# audioAmp.net
KiCad netlist of a schematic drawn in EAGLE
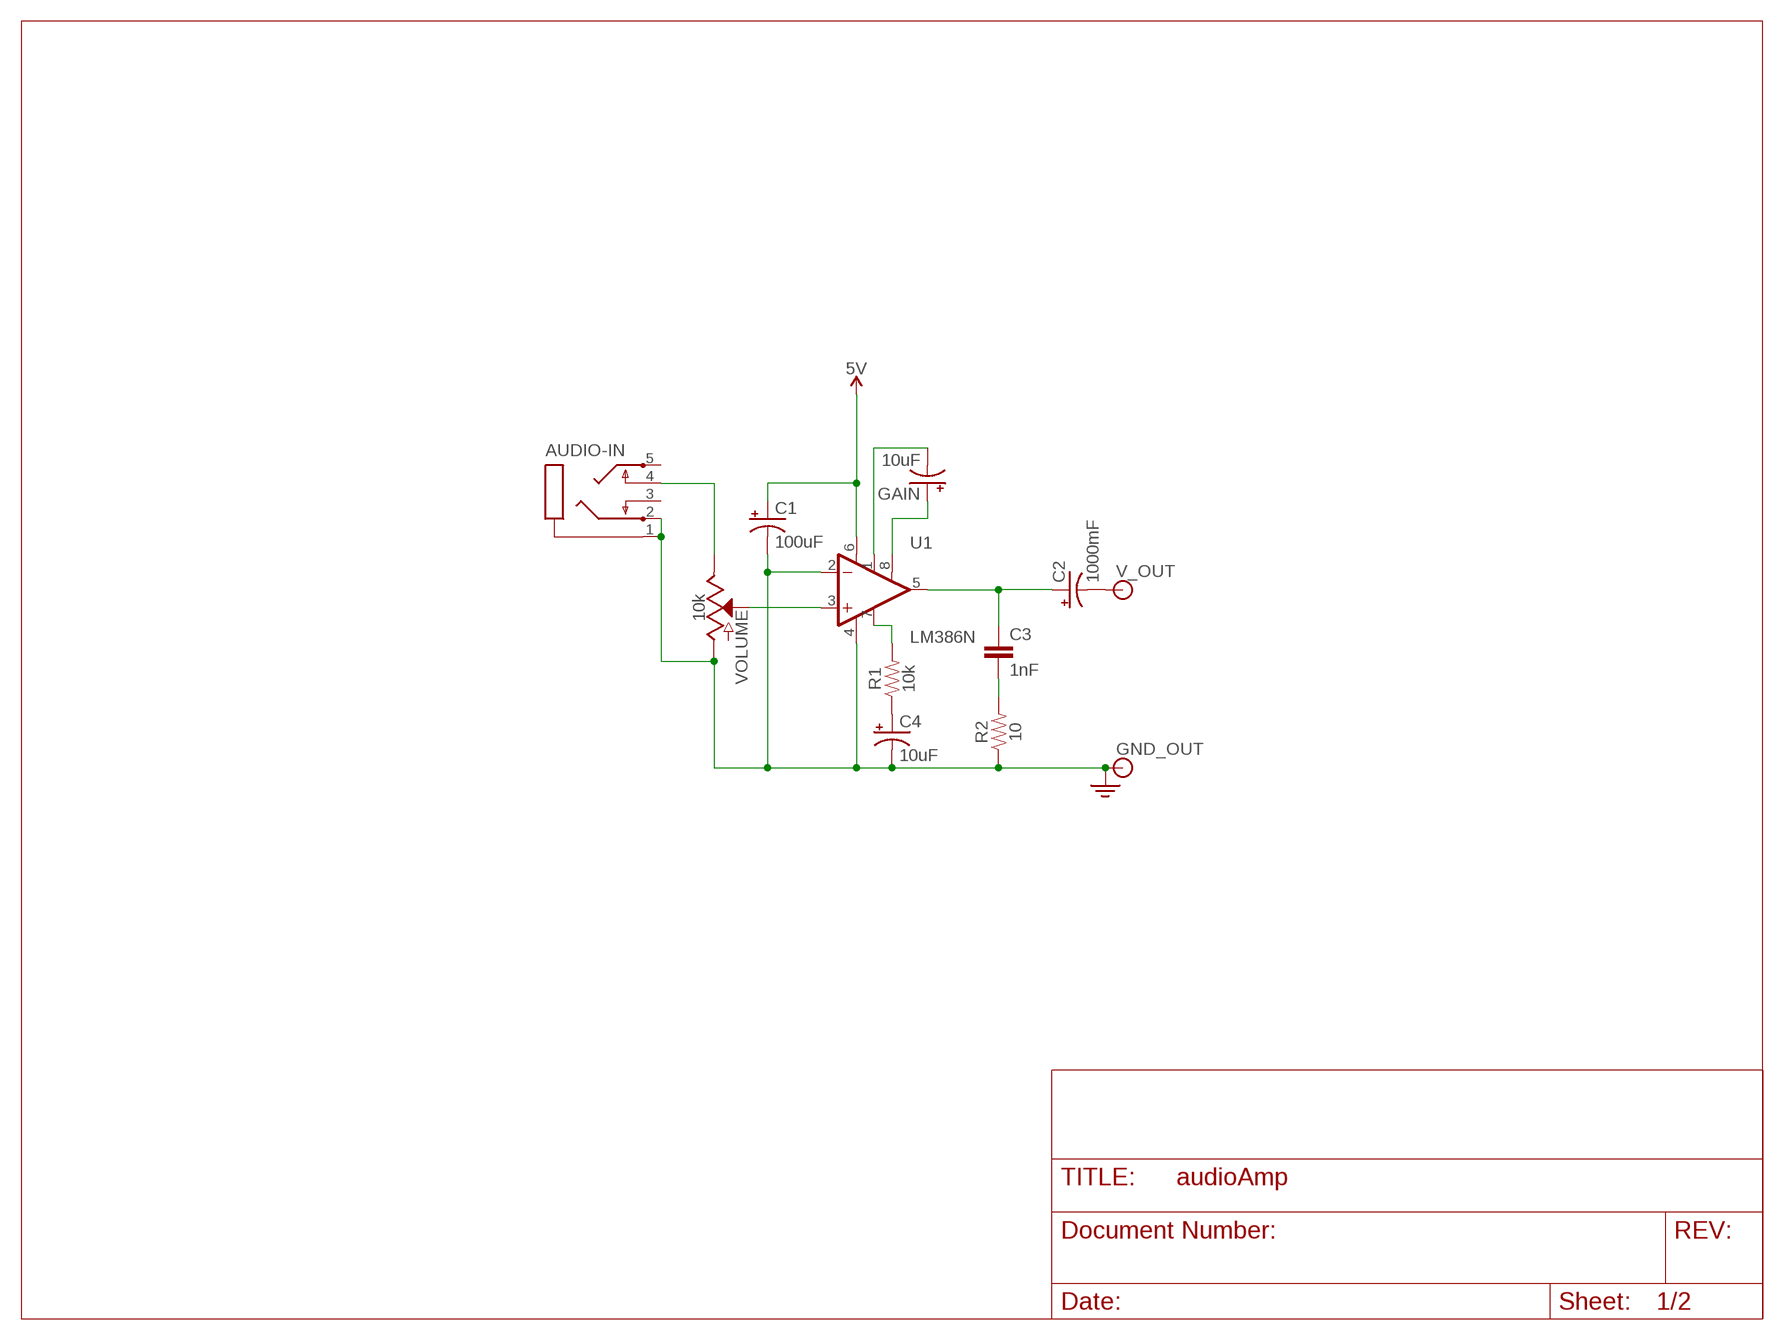
[diagram p0: schematic, sheet 1]
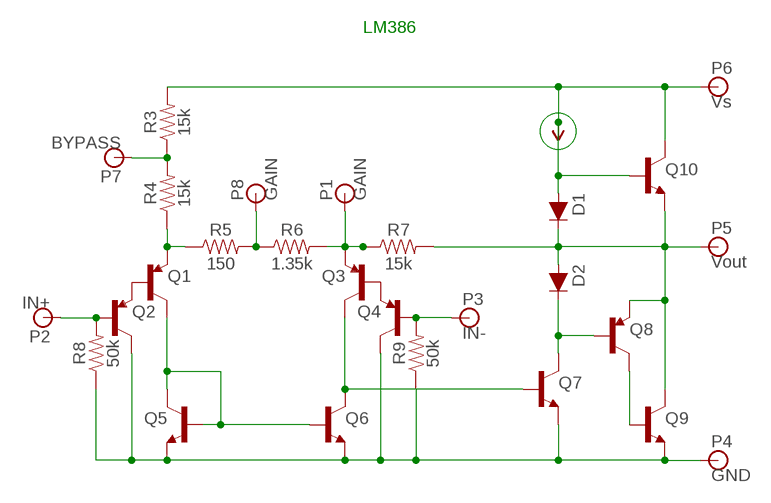
[diagram p1: schematic, sheet 2]

(export (version "E")
  (design (tool "Eeschema 10.0.6"))
  (components
    (comp (ref "D1")
      (value "DIODE-1N4148")
      (footprint "eagle-import:DIODE-1N4148")
      (libsource (lib "eagle-import") (part "DIODE-1N4148"))
    )
    (comp (ref "D2")
      (value "DIODE-1N4148")
      (footprint "eagle-import:DIODE-1N4148")
      (libsource (lib "eagle-import") (part "DIODE-1N4148"))
    )
    (comp (ref "P1")
      (value "GAIN")
      (footprint "eagle-import:BANANA_CONN")
      (libsource (lib "eagle-import") (part "BANANA_CONN"))
    )
    (comp (ref "P2")
      (value "IN+")
      (footprint "eagle-import:BANANA_CONN")
      (libsource (lib "eagle-import") (part "BANANA_CONN"))
    )
    (comp (ref "P3")
      (value "IN-")
      (footprint "eagle-import:BANANA_CONN")
      (libsource (lib "eagle-import") (part "BANANA_CONN"))
    )
    (comp (ref "P4")
      (value "GND")
      (footprint "eagle-import:BANANA_CONN")
      (libsource (lib "eagle-import") (part "BANANA_CONN"))
    )
    (comp (ref "P5")
      (value "Vout")
      (footprint "eagle-import:BANANA_CONN")
      (libsource (lib "eagle-import") (part "BANANA_CONN"))
    )
    (comp (ref "P6")
      (value "Vs")
      (footprint "eagle-import:BANANA_CONN")
      (libsource (lib "eagle-import") (part "BANANA_CONN"))
    )
    (comp (ref "P7")
      (value "BYPASS")
      (footprint "eagle-import:BANANA_CONN")
      (libsource (lib "eagle-import") (part "BANANA_CONN"))
    )
    (comp (ref "P8")
      (value "GAIN")
      (footprint "eagle-import:BANANA_CONN")
      (libsource (lib "eagle-import") (part "BANANA_CONN"))
    )
    (comp (ref "Q1")
      (value "TRANS_PNP-MMBT4403")
      (footprint "eagle-import:SOT23-3")
      (libsource (lib "eagle-import") (part "TRANS_PNP-MMBT4403"))
    )
    (comp (ref "Q2")
      (value "TRANS_PNP-MMBT4403")
      (footprint "eagle-import:SOT23-3")
      (libsource (lib "eagle-import") (part "TRANS_PNP-MMBT4403"))
    )
    (comp (ref "Q3")
      (value "TRANS_PNP-MMBT4403")
      (footprint "eagle-import:SOT23-3")
      (libsource (lib "eagle-import") (part "TRANS_PNP-MMBT4403"))
    )
    (comp (ref "Q4")
      (value "TRANS_PNP-MMBT4403")
      (footprint "eagle-import:SOT23-3")
      (libsource (lib "eagle-import") (part "TRANS_PNP-MMBT4403"))
    )
    (comp (ref "Q5")
      (value "TRANS_NPN-MMBT2222AL")
      (footprint "eagle-import:SOT23-3")
      (libsource (lib "eagle-import") (part "TRANS_NPN-MMBT2222AL"))
    )
    (comp (ref "Q6")
      (value "TRANS_NPN-MMBT2222AL")
      (footprint "eagle-import:SOT23-3")
      (libsource (lib "eagle-import") (part "TRANS_NPN-MMBT2222AL"))
    )
    (comp (ref "Q7")
      (value "TRANS_NPN-MMBT2222AL")
      (footprint "eagle-import:SOT23-3")
      (libsource (lib "eagle-import") (part "TRANS_NPN-MMBT2222AL"))
    )
    (comp (ref "Q8")
      (value "TRANS_PNP-MMBT4403")
      (footprint "eagle-import:SOT23-3")
      (libsource (lib "eagle-import") (part "TRANS_PNP-MMBT4403"))
    )
    (comp (ref "Q9")
      (value "TRANS_NPN-MMBT2222AL")
      (footprint "eagle-import:SOT23-3")
      (libsource (lib "eagle-import") (part "TRANS_NPN-MMBT2222AL"))
    )
    (comp (ref "Q10")
      (value "TRANS_NPN-MMBT2222AL")
      (footprint "eagle-import:SOT23-3")
      (libsource (lib "eagle-import") (part "TRANS_NPN-MMBT2222AL"))
    )
    (comp (ref "R3")
      (value "15k")
      (footprint "eagle-import:AXIAL-0.3")
      (libsource (lib "eagle-import") (part "15KOHM-HORIZ-1/4W-5%"))
    )
    (comp (ref "R4")
      (value "15k")
      (footprint "eagle-import:AXIAL-0.3")
      (libsource (lib "eagle-import") (part "15KOHM-HORIZ-1/4W-5%"))
    )
    (comp (ref "R5")
      (value "150")
      (footprint "eagle-import:AXIAL-0.3")
      (libsource (lib "eagle-import") (part "RESISTORAXIAL-0.3"))
    )
    (comp (ref "R6")
      (value "1.35k")
      (footprint "eagle-import:AXIAL-0.3")
      (libsource (lib "eagle-import") (part "RESISTORAXIAL-0.3"))
    )
    (comp (ref "R7")
      (value "15k")
      (footprint "eagle-import:AXIAL-0.3")
      (libsource (lib "eagle-import") (part "RESISTORAXIAL-0.3"))
    )
    (comp (ref "R8")
      (value "50k")
      (footprint "eagle-import:AXIAL-0.3")
      (libsource (lib "eagle-import") (part "RESISTORAXIAL-0.3"))
    )
    (comp (ref "R9")
      (value "50k")
      (footprint "eagle-import:AXIAL-0.3")
      (libsource (lib "eagle-import") (part "RESISTORAXIAL-0.3"))
    )
    (comp (ref "AUDIO-IN")
      (value "STEREOJACK")
      (footprint "eagle-import:STX3100")
      (libsource (lib "eagle-import") (part "STEREOJACK"))
    )
    (comp (ref "C1")
      (value "100uF")
      (footprint "eagle-import:CPOL-RADIAL-2.5MM-6.5MM")
      (libsource (lib "eagle-import") (part "100UF-POLAR-RADIAL-2.5MM-25V-20%"))
    )
    (comp (ref "C2")
      (value "1000mF")
      (footprint "eagle-import:CPOL-RADIAL-5MM-10MM")
      (libsource (lib "eagle-import") (part "1000UF-RADIAL-5MM-25V-20%"))
    )
    (comp (ref "C3")
      (value "1nF")
      (footprint "eagle-import:0603")
      (libsource (lib "eagle-import") (part "1.0NF/1000PF-0603-50V-10%"))
    )
    (comp (ref "C4")
      (value "10uF")
      (footprint "eagle-import:CPOL-RADIAL-2.5MM-5MM")
      (libsource (lib "eagle-import") (part "10UF-POLAR-RADIAL-2.5MM-25V-20%"))
    )
    (comp (ref "GAIN")
      (value "10uF")
      (footprint "eagle-import:CPOL-RADIAL-2.5MM-5MM")
      (libsource (lib "eagle-import") (part "10UF-POLAR-RADIAL-2.5MM-25V-20%"))
    )
    (comp (ref "GND_OUT")
      (value "BANANA_CONN")
      (footprint "eagle-import:BANANA_CONN")
      (libsource (lib "eagle-import") (part "BANANA_CONN"))
    )
    (comp (ref "R1")
      (value "10k")
      (footprint "eagle-import:AXIAL-0.3")
      (libsource (lib "eagle-import") (part "10KOHM-HORIZ-1/4W-1%"))
    )
    (comp (ref "R2")
      (value "10")
      (footprint "eagle-import:AXIAL-0.3")
      (libsource (lib "eagle-import") (part "10OHM-HORIZ-1/4W-1%"))
    )
    (comp (ref "U1")
      (value "LM386N")
      (footprint "eagle-import:DIP08")
      (libsource (lib "eagle-import") (part "LM386"))
    )
    (comp (ref "VOLUME")
      (value "10k")
      (footprint "eagle-import:POT-PTH-ALPS")
      (libsource (lib "eagle-import") (part "POTENTIOMETER-PTH-9MM-1/20W-20%"))
    )
    (comp (ref "V_OUT")
      (value "BANANA_CONN")
      (footprint "eagle-import:BANANA_CONN")
      (libsource (lib "eagle-import") (part "BANANA_CONN"))
    )
  )
  (nets
    (net (code "1") (name "5V") (class "Default")
      (node (ref "C1") (pin "1") (pinfunction "+_1") (pintype "passive"))
      (node (ref "U1") (pin "6") (pinfunction "V+_6") (pintype "power_in"))
    )
    (net (code "2") (name "GND2") (class "Default")
      (node (ref "AUDIO-IN") (pin "1") (pinfunction "1_1") (pintype "passive"))
      (node (ref "AUDIO-IN") (pin "2") (pinfunction "2_2") (pintype "passive"))
      (node (ref "C1") (pin "2") (pinfunction "-_2") (pintype "passive"))
      (node (ref "C4") (pin "2") (pinfunction "-_2") (pintype "passive"))
      (node (ref "GND_OUT") (pin "P$1") (pinfunction "1_P$1") (pintype "passive"))
      (node (ref "R2") (pin "P$1") (pinfunction "1_P$1") (pintype "passive"))
      (node (ref "U1") (pin "2") (pinfunction "-IN_2") (pintype "input"))
      (node (ref "U1") (pin "4") (pinfunction "V-_4") (pintype "power_in"))
      (node (ref "VOLUME") (pin "P$3") (pinfunction "A_P$3") (pintype "passive"))
    )
    (net (code "3") (name "Net-(C4-+)") (class "Default")
      (node (ref "C4") (pin "1") (pinfunction "+_1") (pintype "passive"))
      (node (ref "R1") (pin "P$1") (pinfunction "1_P$1") (pintype "passive"))
    )
    (net (code "4") (name "Net-(GAIN-+)") (class "Default")
      (node (ref "GAIN") (pin "1") (pinfunction "+_1") (pintype "passive"))
      (node (ref "U1") (pin "8") (pinfunction "GAIN_8") (pintype "bidirectional"))
    )
    (net (code "5") (name "Net-(GAIN--)") (class "Default")
      (node (ref "GAIN") (pin "2") (pinfunction "-_2") (pintype "passive"))
      (node (ref "U1") (pin "1") (pinfunction "GAIN_1") (pintype "bidirectional"))
    )
    (net (code "6") (name "Net-(P1-1)") (class "Default")
      (node (ref "P1") (pin "P$1") (pinfunction "1_P$1") (pintype "passive"))
      (node (ref "Q3") (pin "2") (pinfunction "E_2") (pintype "passive"))
      (node (ref "R6") (pin "P$2") (pinfunction "2_P$2") (pintype "passive"))
      (node (ref "R7") (pin "P$1") (pinfunction "1_P$1") (pintype "passive"))
    )
    (net (code "7") (name "Net-(P2-1)") (class "Default")
      (node (ref "P2") (pin "P$1") (pinfunction "1_P$1") (pintype "passive"))
      (node (ref "Q2") (pin "1") (pinfunction "B_1") (pintype "passive"))
      (node (ref "R8") (pin "P$2") (pinfunction "2_P$2") (pintype "passive"))
    )
    (net (code "8") (name "Net-(P3-1)") (class "Default")
      (node (ref "P3") (pin "P$1") (pinfunction "1_P$1") (pintype "passive"))
      (node (ref "Q4") (pin "1") (pinfunction "B_1") (pintype "passive"))
      (node (ref "R9") (pin "P$2") (pinfunction "2_P$2") (pintype "passive"))
    )
    (net (code "9") (name "Net-(P4-1)") (class "Default")
      (node (ref "P4") (pin "P$1") (pinfunction "1_P$1") (pintype "passive"))
      (node (ref "Q2") (pin "3") (pinfunction "C_3") (pintype "passive"))
      (node (ref "Q4") (pin "3") (pinfunction "C_3") (pintype "passive"))
      (node (ref "Q5") (pin "2") (pinfunction "E_2") (pintype "passive"))
      (node (ref "Q6") (pin "2") (pinfunction "E_2") (pintype "passive"))
      (node (ref "Q7") (pin "2") (pinfunction "E_2") (pintype "passive"))
      (node (ref "Q9") (pin "2") (pinfunction "E_2") (pintype "passive"))
      (node (ref "R8") (pin "P$1") (pinfunction "1_P$1") (pintype "passive"))
      (node (ref "R9") (pin "P$1") (pinfunction "1_P$1") (pintype "passive"))
    )
    (net (code "10") (name "Net-(P5-1)") (class "Default")
      (node (ref "D1") (pin "C") (pinfunction "C_C") (pintype "passive"))
      (node (ref "D2") (pin "A") (pinfunction "A_A") (pintype "passive"))
      (node (ref "P5") (pin "P$1") (pinfunction "1_P$1") (pintype "passive"))
      (node (ref "Q10") (pin "2") (pinfunction "E_2") (pintype "passive"))
      (node (ref "Q8") (pin "2") (pinfunction "E_2") (pintype "passive"))
      (node (ref "Q9") (pin "3") (pinfunction "C_3") (pintype "passive"))
      (node (ref "R7") (pin "P$2") (pinfunction "2_P$2") (pintype "passive"))
    )
    (net (code "11") (name "Net-(P7-1)") (class "Default")
      (node (ref "P7") (pin "P$1") (pinfunction "1_P$1") (pintype "passive"))
      (node (ref "R3") (pin "P$1") (pinfunction "1_P$1") (pintype "passive"))
      (node (ref "R4") (pin "P$2") (pinfunction "2_P$2") (pintype "passive"))
    )
    (net (code "12") (name "Net-(P8-1)") (class "Default")
      (node (ref "P8") (pin "P$1") (pinfunction "1_P$1") (pintype "passive"))
      (node (ref "R5") (pin "P$2") (pinfunction "2_P$2") (pintype "passive"))
      (node (ref "R6") (pin "P$1") (pinfunction "1_P$1") (pintype "passive"))
    )
    (net (code "13") (name "Net-(Q1-B)") (class "Default")
      (node (ref "Q1") (pin "1") (pinfunction "B_1") (pintype "passive"))
      (node (ref "Q2") (pin "2") (pinfunction "E_2") (pintype "passive"))
    )
    (net (code "14") (name "Net-(Q1-C)") (class "Default")
      (node (ref "Q1") (pin "3") (pinfunction "C_3") (pintype "passive"))
      (node (ref "Q5") (pin "1") (pinfunction "B_1") (pintype "passive"))
      (node (ref "Q5") (pin "3") (pinfunction "C_3") (pintype "passive"))
      (node (ref "Q6") (pin "1") (pinfunction "B_1") (pintype "passive"))
    )
    (net (code "15") (name "Net-(Q1-E)") (class "Default")
      (node (ref "Q1") (pin "2") (pinfunction "E_2") (pintype "passive"))
      (node (ref "R4") (pin "P$1") (pinfunction "1_P$1") (pintype "passive"))
      (node (ref "R5") (pin "P$1") (pinfunction "1_P$1") (pintype "passive"))
    )
    (net (code "16") (name "Net-(Q3-B)") (class "Default")
      (node (ref "Q3") (pin "1") (pinfunction "B_1") (pintype "passive"))
      (node (ref "Q4") (pin "2") (pinfunction "E_2") (pintype "passive"))
    )
    (net (code "17") (name "Net-(Q3-C)") (class "Default")
      (node (ref "Q3") (pin "3") (pinfunction "C_3") (pintype "passive"))
      (node (ref "Q6") (pin "3") (pinfunction "C_3") (pintype "passive"))
      (node (ref "Q7") (pin "1") (pinfunction "B_1") (pintype "passive"))
    )
    (net (code "18") (name "Net-(Q7-C)") (class "Default")
      (node (ref "D2") (pin "C") (pinfunction "C_C") (pintype "passive"))
      (node (ref "Q7") (pin "3") (pinfunction "C_3") (pintype "passive"))
      (node (ref "Q8") (pin "1") (pinfunction "B_1") (pintype "passive"))
    )
    (net (code "19") (name "Net-(Q8-C)") (class "Default")
      (node (ref "Q8") (pin "3") (pinfunction "C_3") (pintype "passive"))
      (node (ref "Q9") (pin "1") (pinfunction "B_1") (pintype "passive"))
    )
    (net (code "20") (name "Net-(R1-2)") (class "Default")
      (node (ref "R1") (pin "P$2") (pinfunction "2_P$2") (pintype "passive"))
      (node (ref "U1") (pin "7") (pinfunction "BP_7") (pintype "bidirectional"))
    )
    (net (code "21") (name "Net-(R2-2)") (class "Default")
      (node (ref "C3") (pin "2") (pinfunction "2_2") (pintype "passive"))
      (node (ref "R2") (pin "P$2") (pinfunction "2_P$2") (pintype "passive"))
    )
    (net (code "22") (name "Net-(U1-+IN)") (class "Default")
      (node (ref "U1") (pin "3") (pinfunction "+IN_3") (pintype "input"))
      (node (ref "VOLUME") (pin "P$2") (pinfunction "S_P$2") (pintype "passive"))
    )
    (net (code "23") (name "Net-(U1-OUT)") (class "Default")
      (node (ref "C2") (pin "+") (pinfunction "+_+") (pintype "passive"))
      (node (ref "C3") (pin "1") (pinfunction "1_1") (pintype "passive"))
      (node (ref "U1") (pin "5") (pinfunction "OUT_5") (pintype "output"))
    )
    (net (code "24") (name "Net-(VOLUME-E)") (class "Default")
      (node (ref "AUDIO-IN") (pin "4") (pinfunction "4_4") (pintype "passive"))
      (node (ref "VOLUME") (pin "P$1") (pinfunction "E_P$1") (pintype "passive"))
    )
    (net (code "25") (name "Net-(V_OUT-1)") (class "Default")
      (node (ref "C2") (pin "-") (pinfunction "-_-") (pintype "passive"))
      (node (ref "V_OUT") (pin "P$1") (pinfunction "1_P$1") (pintype "passive"))
    )
    (net (code "26") (name "VNEG") (class "Default")
      (node (ref "D1") (pin "A") (pinfunction "A_A") (pintype "passive"))
      (node (ref "P6") (pin "P$1") (pinfunction "1_P$1") (pintype "passive"))
      (node (ref "Q10") (pin "1") (pinfunction "B_1") (pintype "passive"))
      (node (ref "Q10") (pin "3") (pinfunction "C_3") (pintype "passive"))
      (node (ref "R3") (pin "P$2") (pinfunction "2_P$2") (pintype "passive"))
    )
    (net (code "27") (name "unconnected-(AUDIO-IN-Pad3)") (class "Default")
      (node (ref "AUDIO-IN") (pin "3") (pinfunction "3_3") (pintype "passive"))
    )
    (net (code "28") (name "unconnected-(AUDIO-IN-Pad5)") (class "Default")
      (node (ref "AUDIO-IN") (pin "5") (pinfunction "5_5") (pintype "passive"))
    )
  )
)
